# BTLED-01.net
KiCad netlist of a schematic drawn in EAGLE
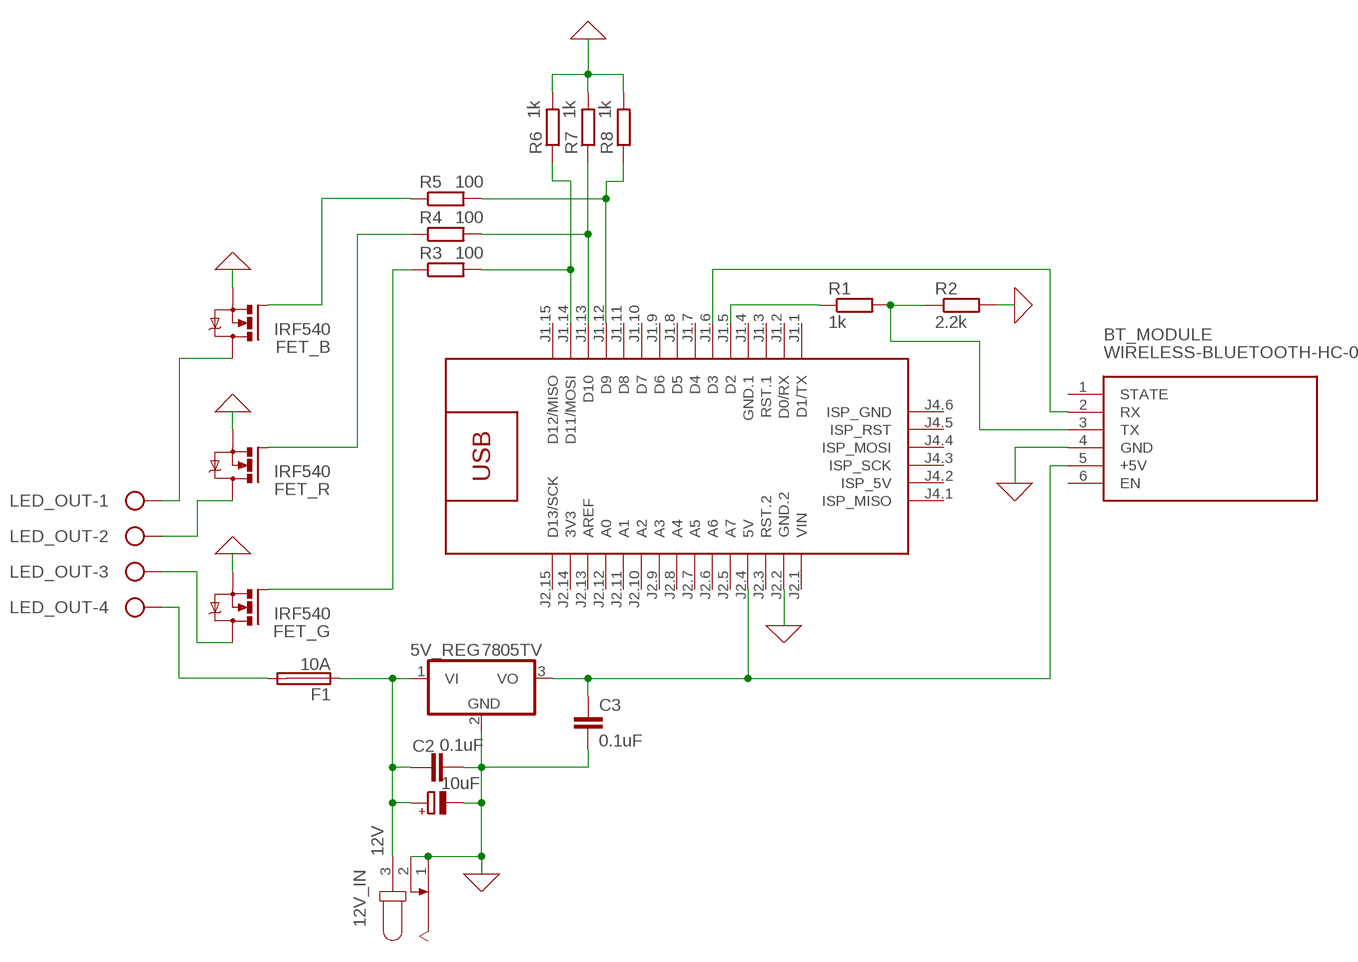
[diagram p0: schematic, sheet 1]

(export (version "E")
  (design (tool "Eeschema 10.0.6"))
  (components
    (comp (ref "5V_REG")
      (value "7805TV")
      (footprint "eagle-import:TO220V")
      (libsource (lib "eagle-import") (part "78TV05"))
    )
    (comp (ref "12V_IN")
      (value "12V")
      (footprint "eagle-import:SPC4078")
      (libsource (lib "eagle-import") (part "JACK-PLUG1"))
    )
    (comp (ref "ARDUINO_NANO")
      (value "ARDUINO-NANO-3.0#ISP")
      (footprint "eagle-import:ARDUINO-NANO-3.0#ISP")
      (libsource (lib "eagle-import") (part "ARDUINO-NANO-3.0#ISP"))
    )
    (comp (ref "BT_MODULE")
      (value "WIRELESS-BLUETOOTH-HC-05")
      (footprint "eagle-import:WIRELESS-BLUETOOTH-HC-05")
      (libsource (lib "eagle-import") (part "WIRELESS-BLUETOOTH-HC-05"))
    )
    (comp (ref "C1")
      (value "10uF")
      (footprint "eagle-import:E2,5-6")
      (libsource (lib "eagle-import") (part "CPOL-EUE2.5-6"))
    )
    (comp (ref "C2")
      (value "0.1uF")
      (footprint "eagle-import:C050-024X044")
      (libsource (lib "eagle-import") (part "C-EU050-024X044"))
    )
    (comp (ref "C3")
      (value "0.1uF")
      (footprint "eagle-import:C050-024X044")
      (libsource (lib "eagle-import") (part "C-EU050-024X044"))
    )
    (comp (ref "F1")
      (value "10A")
      (footprint "eagle-import:SH22,5")
      (fields (field (name "MF") "SCHURTER") (field (name "MPN") "0031.8201"))
      (libsource (lib "eagle-import") (part "SH22,5"))
    )
    (comp (ref "FET_B")
      (value "IRF540")
      (footprint "eagle-import:TO220BV")
      (libsource (lib "eagle-import") (part "IRF540"))
    )
    (comp (ref "FET_G")
      (value "IRF540")
      (footprint "eagle-import:TO220BV")
      (libsource (lib "eagle-import") (part "IRF540"))
    )
    (comp (ref "FET_R")
      (value "IRF540")
      (footprint "eagle-import:TO220BV")
      (libsource (lib "eagle-import") (part "IRF540"))
    )
    (comp (ref "LED_OUT")
      (value "W237-4")
      (footprint "eagle-import:W237-4")
      (libsource (lib "eagle-import") (part "W237-4"))
    )
    (comp (ref "R1")
      (value "1k")
      (footprint "eagle-import:0204_7")
      (libsource (lib "eagle-import") (part "R-EU_0204/7"))
    )
    (comp (ref "R2")
      (value "2.2k")
      (footprint "eagle-import:0204_7")
      (libsource (lib "eagle-import") (part "R-EU_0204/7"))
    )
    (comp (ref "R3")
      (value "100")
      (footprint "eagle-import:0204_7")
      (libsource (lib "eagle-import") (part "R-EU_0204/7"))
    )
    (comp (ref "R4")
      (value "100")
      (footprint "eagle-import:0204_7")
      (libsource (lib "eagle-import") (part "R-EU_0204/7"))
    )
    (comp (ref "R5")
      (value "100")
      (footprint "eagle-import:0204_7")
      (libsource (lib "eagle-import") (part "R-EU_0204/7"))
    )
    (comp (ref "R6")
      (value "1k")
      (footprint "eagle-import:0204_7")
      (libsource (lib "eagle-import") (part "R-EU_0204/7"))
    )
    (comp (ref "R7")
      (value "1k")
      (footprint "eagle-import:0204_7")
      (libsource (lib "eagle-import") (part "R-EU_0204/7"))
    )
    (comp (ref "R8")
      (value "1k")
      (footprint "eagle-import:0204_7")
      (libsource (lib "eagle-import") (part "R-EU_0204/7"))
    )
  )
  (nets
    (net (code "1") (name "/3V3") (class "Default")
      (node (ref "ARDUINO_NANO") (pin "J2.14") (pinfunction "3V3_J2.14") (pintype "power_in"))
    )
    (net (code "2") (name "/GND.1") (class "Default")
      (node (ref "ARDUINO_NANO") (pin "J1.4") (pinfunction "GND.1_J1.4") (pintype "power_in"))
    )
    (net (code "3") (name "/VIN") (class "Default")
      (node (ref "ARDUINO_NANO") (pin "J2.1") (pinfunction "VIN_J2.1") (pintype "power_in"))
    )
    (net (code "4") (name "GND") (class "Default")
      (node (ref "12V_IN") (pin "1") (pinfunction "1_1") (pintype "passive"))
      (node (ref "12V_IN") (pin "2") (pinfunction "2_2") (pintype "passive"))
      (node (ref "5V_REG") (pin "2") (pinfunction "GND_2") (pintype "passive"))
      (node (ref "ARDUINO_NANO") (pin "J2.2") (pinfunction "GND.2_J2.2") (pintype "power_in"))
      (node (ref "BT_MODULE") (pin "4") (pinfunction "GND_4") (pintype "power_in"))
      (node (ref "C1") (pin "-") (pinfunction "-_-") (pintype "passive"))
      (node (ref "C2") (pin "2") (pinfunction "2_2") (pintype "passive"))
      (node (ref "C3") (pin "2") (pinfunction "2_2") (pintype "passive"))
      (node (ref "FET_B") (pin "S") (pinfunction "S_S") (pintype "passive"))
      (node (ref "FET_G") (pin "S") (pinfunction "S_S") (pintype "passive"))
      (node (ref "FET_R") (pin "S") (pinfunction "S_S") (pintype "passive"))
      (node (ref "R2") (pin "2") (pinfunction "2_2") (pintype "passive"))
      (node (ref "R6") (pin "2") (pinfunction "2_2") (pintype "passive"))
      (node (ref "R7") (pin "2") (pinfunction "2_2") (pintype "passive"))
      (node (ref "R8") (pin "2") (pinfunction "2_2") (pintype "passive"))
    )
    (net (code "5") (name "Net-(5V_REG-VI)") (class "Default")
      (node (ref "12V_IN") (pin "3") (pinfunction "3_3") (pintype "passive"))
      (node (ref "5V_REG") (pin "1") (pinfunction "VI_1") (pintype "input"))
      (node (ref "C1") (pin "+") (pinfunction "+_+") (pintype "passive"))
      (node (ref "C2") (pin "1") (pinfunction "1_1") (pintype "passive"))
      (node (ref "F1") (pin "1") (pinfunction "1_1") (pintype "passive"))
    )
    (net (code "6") (name "Net-(5V_REG-VO)") (class "Default")
      (node (ref "5V_REG") (pin "3") (pinfunction "VO_3") (pintype "passive"))
      (node (ref "ARDUINO_NANO") (pin "J2.4") (pinfunction "5V_J2.4") (pintype "power_in"))
      (node (ref "BT_MODULE") (pin "5") (pinfunction "+5V_5") (pintype "power_in"))
      (node (ref "C3") (pin "1") (pinfunction "1_1") (pintype "passive"))
    )
    (net (code "7") (name "Net-(ARDUINO_NANO-D2)") (class "Default")
      (node (ref "ARDUINO_NANO") (pin "J1.5") (pinfunction "D2_J1.5") (pintype "bidirectional"))
      (node (ref "R1") (pin "1") (pinfunction "1_1") (pintype "passive"))
    )
    (net (code "8") (name "Net-(ARDUINO_NANO-D3)") (class "Default")
      (node (ref "ARDUINO_NANO") (pin "J1.6") (pinfunction "D3_J1.6") (pintype "bidirectional"))
      (node (ref "BT_MODULE") (pin "2") (pinfunction "RX_2") (pintype "bidirectional"))
    )
    (net (code "9") (name "Net-(ARDUINO_NANO-D9)") (class "Default")
      (node (ref "ARDUINO_NANO") (pin "J1.12") (pinfunction "D9_J1.12") (pintype "bidirectional"))
      (node (ref "R5") (pin "2") (pinfunction "2_2") (pintype "passive"))
      (node (ref "R8") (pin "1") (pinfunction "1_1") (pintype "passive"))
    )
    (net (code "10") (name "Net-(ARDUINO_NANO-D10)") (class "Default")
      (node (ref "ARDUINO_NANO") (pin "J1.13") (pinfunction "D10_J1.13") (pintype "bidirectional"))
      (node (ref "R4") (pin "2") (pinfunction "2_2") (pintype "passive"))
      (node (ref "R7") (pin "1") (pinfunction "1_1") (pintype "passive"))
    )
    (net (code "11") (name "Net-(ARDUINO_NANO-D11{slash}MOSI)") (class "Default")
      (node (ref "ARDUINO_NANO") (pin "J1.14") (pinfunction "D11/MOSI_J1.14") (pintype "bidirectional"))
      (node (ref "R3") (pin "2") (pinfunction "2_2") (pintype "passive"))
      (node (ref "R6") (pin "1") (pinfunction "1_1") (pintype "passive"))
    )
    (net (code "12") (name "Net-(BT_MODULE-TX)") (class "Default")
      (node (ref "BT_MODULE") (pin "3") (pinfunction "TX_3") (pintype "bidirectional"))
      (node (ref "R1") (pin "2") (pinfunction "2_2") (pintype "passive"))
      (node (ref "R2") (pin "1") (pinfunction "1_1") (pintype "passive"))
    )
    (net (code "13") (name "Net-(FET_B-PadG)") (class "Default")
      (node (ref "FET_B") (pin "G") (pinfunction "G_G") (pintype "passive"))
      (node (ref "R5") (pin "1") (pinfunction "1_1") (pintype "passive"))
    )
    (net (code "14") (name "Net-(FET_G-PadG)") (class "Default")
      (node (ref "FET_G") (pin "G") (pinfunction "G_G") (pintype "passive"))
      (node (ref "R3") (pin "1") (pinfunction "1_1") (pintype "passive"))
    )
    (net (code "15") (name "Net-(FET_R-PadG)") (class "Default")
      (node (ref "FET_R") (pin "G") (pinfunction "G_G") (pintype "passive"))
      (node (ref "R4") (pin "1") (pinfunction "1_1") (pintype "passive"))
    )
    (net (code "16") (name "Net-(LED_OUTA-KL)") (class "Default")
      (node (ref "FET_B") (pin "D") (pinfunction "D_D") (pintype "passive"))
      (node (ref "LED_OUT") (pin "1") (pinfunction "KL_1") (pintype "passive"))
    )
    (net (code "17") (name "Net-(LED_OUTB-KL)") (class "Default")
      (node (ref "FET_R") (pin "D") (pinfunction "D_D") (pintype "passive"))
      (node (ref "LED_OUT") (pin "2") (pinfunction "KL_2") (pintype "passive"))
    )
    (net (code "18") (name "Net-(LED_OUTC-KL)") (class "Default")
      (node (ref "FET_G") (pin "D") (pinfunction "D_D") (pintype "passive"))
      (node (ref "LED_OUT") (pin "3") (pinfunction "KL_3") (pintype "passive"))
    )
    (net (code "19") (name "Net-(LED_OUTD-KL)") (class "Default")
      (node (ref "F1") (pin "2") (pinfunction "2_2") (pintype "passive"))
      (node (ref "LED_OUT") (pin "4") (pinfunction "KL_4") (pintype "passive"))
    )
    (net (code "20") (name "unconnected-(ARDUINO_NANO-A0-PadJ2.12)") (class "Default")
      (node (ref "ARDUINO_NANO") (pin "J2.12") (pinfunction "A0_J2.12") (pintype "bidirectional"))
    )
    (net (code "21") (name "unconnected-(ARDUINO_NANO-A1-PadJ2.11)") (class "Default")
      (node (ref "ARDUINO_NANO") (pin "J2.11") (pinfunction "A1_J2.11") (pintype "bidirectional"))
    )
    (net (code "22") (name "unconnected-(ARDUINO_NANO-A2-PadJ2.10)") (class "Default")
      (node (ref "ARDUINO_NANO") (pin "J2.10") (pinfunction "A2_J2.10") (pintype "bidirectional"))
    )
    (net (code "23") (name "unconnected-(ARDUINO_NANO-A3-PadJ2.9)") (class "Default")
      (node (ref "ARDUINO_NANO") (pin "J2.9") (pinfunction "A3_J2.9") (pintype "bidirectional"))
    )
    (net (code "24") (name "unconnected-(ARDUINO_NANO-A4-PadJ2.8)") (class "Default")
      (node (ref "ARDUINO_NANO") (pin "J2.8") (pinfunction "A4_J2.8") (pintype "bidirectional"))
    )
    (net (code "25") (name "unconnected-(ARDUINO_NANO-A5-PadJ2.7)") (class "Default")
      (node (ref "ARDUINO_NANO") (pin "J2.7") (pinfunction "A5_J2.7") (pintype "bidirectional"))
    )
    (net (code "26") (name "unconnected-(ARDUINO_NANO-A6-PadJ2.6)") (class "Default")
      (node (ref "ARDUINO_NANO") (pin "J2.6") (pinfunction "A6_J2.6") (pintype "bidirectional"))
    )
    (net (code "27") (name "unconnected-(ARDUINO_NANO-A7-PadJ2.5)") (class "Default")
      (node (ref "ARDUINO_NANO") (pin "J2.5") (pinfunction "A7_J2.5") (pintype "bidirectional"))
    )
    (net (code "28") (name "unconnected-(ARDUINO_NANO-AREF-PadJ2.13)") (class "Default")
      (node (ref "ARDUINO_NANO") (pin "J2.13") (pinfunction "AREF_J2.13") (pintype "bidirectional"))
    )
    (net (code "29") (name "unconnected-(ARDUINO_NANO-D0{slash}RX-PadJ1.2)") (class "Default")
      (node (ref "ARDUINO_NANO") (pin "J1.2") (pinfunction "D0/RX_J1.2") (pintype "bidirectional"))
    )
    (net (code "30") (name "unconnected-(ARDUINO_NANO-D1{slash}TX-PadJ1.1)") (class "Default")
      (node (ref "ARDUINO_NANO") (pin "J1.1") (pinfunction "D1/TX_J1.1") (pintype "bidirectional"))
    )
    (net (code "31") (name "unconnected-(ARDUINO_NANO-D4-PadJ1.7)") (class "Default")
      (node (ref "ARDUINO_NANO") (pin "J1.7") (pinfunction "D4_J1.7") (pintype "bidirectional"))
    )
    (net (code "32") (name "unconnected-(ARDUINO_NANO-D5-PadJ1.8)") (class "Default")
      (node (ref "ARDUINO_NANO") (pin "J1.8") (pinfunction "D5_J1.8") (pintype "bidirectional"))
    )
    (net (code "33") (name "unconnected-(ARDUINO_NANO-D6-PadJ1.9)") (class "Default")
      (node (ref "ARDUINO_NANO") (pin "J1.9") (pinfunction "D6_J1.9") (pintype "bidirectional"))
    )
    (net (code "34") (name "unconnected-(ARDUINO_NANO-D7-PadJ1.10)") (class "Default")
      (node (ref "ARDUINO_NANO") (pin "J1.10") (pinfunction "D7_J1.10") (pintype "bidirectional"))
    )
    (net (code "35") (name "unconnected-(ARDUINO_NANO-D8-PadJ1.11)") (class "Default")
      (node (ref "ARDUINO_NANO") (pin "J1.11") (pinfunction "D8_J1.11") (pintype "bidirectional"))
    )
    (net (code "36") (name "unconnected-(ARDUINO_NANO-D12{slash}MISO-PadJ1.15)") (class "Default")
      (node (ref "ARDUINO_NANO") (pin "J1.15") (pinfunction "D12/MISO_J1.15") (pintype "bidirectional"))
    )
    (net (code "37") (name "unconnected-(ARDUINO_NANO-D13{slash}SCK-PadJ2.15)") (class "Default")
      (node (ref "ARDUINO_NANO") (pin "J2.15") (pinfunction "D13/SCK_J2.15") (pintype "bidirectional"))
    )
    (net (code "38") (name "unconnected-(ARDUINO_NANO-ISP_5V-PadJ4.2)") (class "Default")
      (node (ref "ARDUINO_NANO") (pin "J4.2") (pinfunction "ISP_5V_J4.2") (pintype "bidirectional"))
    )
    (net (code "39") (name "unconnected-(ARDUINO_NANO-ISP_GND-PadJ4.6)") (class "Default")
      (node (ref "ARDUINO_NANO") (pin "J4.6") (pinfunction "ISP_GND_J4.6") (pintype "bidirectional"))
    )
    (net (code "40") (name "unconnected-(ARDUINO_NANO-ISP_MISO-PadJ4.1)") (class "Default")
      (node (ref "ARDUINO_NANO") (pin "J4.1") (pinfunction "ISP_MISO_J4.1") (pintype "bidirectional"))
    )
    (net (code "41") (name "unconnected-(ARDUINO_NANO-ISP_MOSI-PadJ4.4)") (class "Default")
      (node (ref "ARDUINO_NANO") (pin "J4.4") (pinfunction "ISP_MOSI_J4.4") (pintype "bidirectional"))
    )
    (net (code "42") (name "unconnected-(ARDUINO_NANO-ISP_RST-PadJ4.5)") (class "Default")
      (node (ref "ARDUINO_NANO") (pin "J4.5") (pinfunction "ISP_RST_J4.5") (pintype "bidirectional"))
    )
    (net (code "43") (name "unconnected-(ARDUINO_NANO-ISP_SCK-PadJ4.3)") (class "Default")
      (node (ref "ARDUINO_NANO") (pin "J4.3") (pinfunction "ISP_SCK_J4.3") (pintype "bidirectional"))
    )
    (net (code "44") (name "unconnected-(ARDUINO_NANO-RST.1-PadJ1.3)") (class "Default")
      (node (ref "ARDUINO_NANO") (pin "J1.3") (pinfunction "RST.1_J1.3") (pintype "bidirectional"))
    )
    (net (code "45") (name "unconnected-(ARDUINO_NANO-RST.2-PadJ2.3)") (class "Default")
      (node (ref "ARDUINO_NANO") (pin "J2.3") (pinfunction "RST.2_J2.3") (pintype "bidirectional"))
    )
    (net (code "46") (name "unconnected-(BT_MODULE-EN-Pad6)") (class "Default")
      (node (ref "BT_MODULE") (pin "6") (pinfunction "EN_6") (pintype "bidirectional"))
    )
    (net (code "47") (name "unconnected-(BT_MODULE-STATE-Pad1)") (class "Default")
      (node (ref "BT_MODULE") (pin "1") (pinfunction "STATE_1") (pintype "bidirectional"))
    )
  )
)
